# EasyEDA_sensor_project.net
KiCad netlist of a schematic drawn in EasyEDA Pro
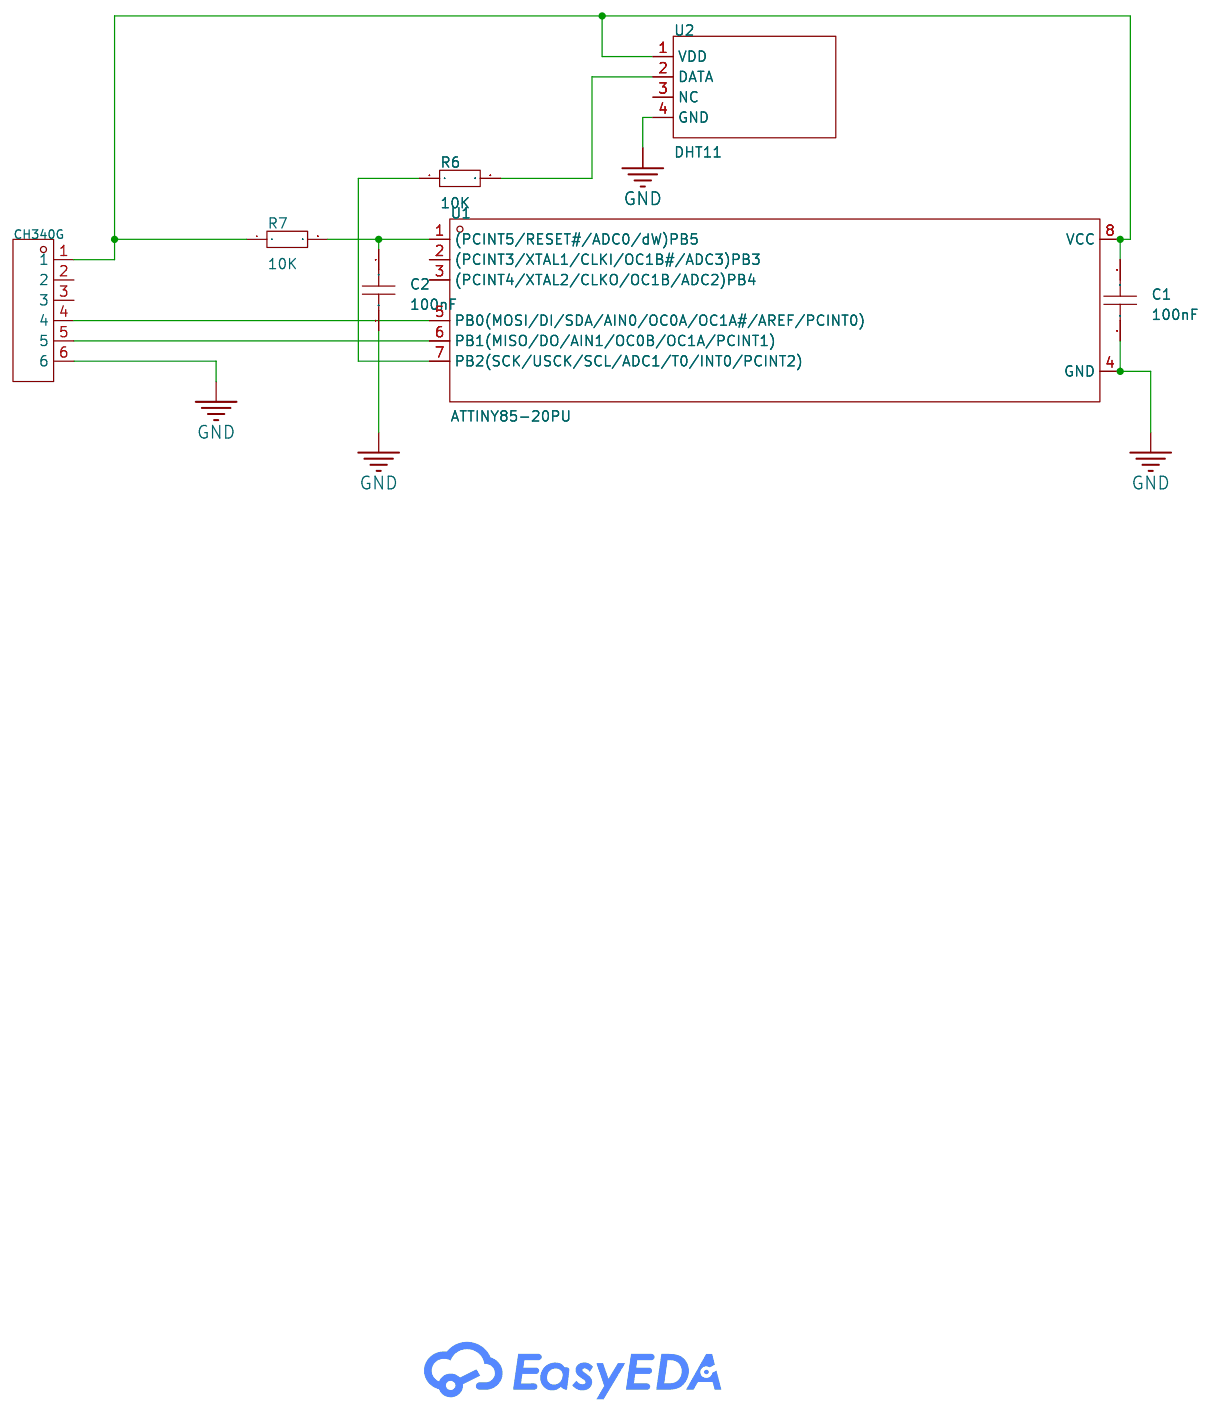
[diagram p0: schematic sheet]

(export (version "E")
  (design (tool "Eeschema 10.0.6"))
  (components
    (comp (ref "C1")
      (value "100nF")
      (footprint "easyedapro:C0201")
      (libsource (lib "easyedapro") (part "CAP"))
    )
    (comp (ref "C2")
      (value "100nF")
      (footprint "easyedapro:C0201")
      (libsource (lib "easyedapro") (part "CAP"))
    )
    (comp (ref "CH340G")
      (value "~")
      (footprint "easyedapro:HDR-TH_6P-P2.54-V-F")
      (libsource (lib "easyedapro") (part "Header-Female-2.54_1x6"))
    )
    (comp (ref "R6") (value "10K") (footprint "easyedapro:R0603") (libsource (lib "easyedapro") (part "Res")))
    (comp (ref "R7") (value "10K") (footprint "easyedapro:R0603") (libsource (lib "easyedapro") (part "Res")))
    (comp (ref "U1")
      (value "ATTINY85-20PU")
      (footprint "easyedapro:PDIP-8_L9.3-W6.4-P2.54-LS7.9-BL-1")
      (fields (field (name "Manufacturer") "MICROCHIP(美国微芯)"))
      (libsource (lib "easyedapro") (part "ATTINY85-20PU"))
    )
    (comp (ref "U2")
      (value "DHT11")
      (footprint "easyedapro:SENSOR-TH_DHT11")
      (fields (field (name "Manufacturer") "广州奥松"))
      (libsource (lib "easyedapro") (part "DHT11"))
    )
  )
  (nets
    (net (code "1") (name "GND") (class "Default")
      (node (ref "C1") (pin "2") (pinfunction "2_2") (pintype "input"))
      (node (ref "C2") (pin "2") (pinfunction "2_2") (pintype "input"))
      (node (ref "CH340G") (pin "6") (pinfunction "6_6") (pintype "input"))
      (node (ref "U1") (pin "4") (pinfunction "GND_4") (pintype "unspecified"))
      (node (ref "U2") (pin "4") (pinfunction "GND_4") (pintype "unspecified"))
    )
    (net (code "2") (name "Net-(U1-(PCINT5{slash}RESET#{slash}ADC0{slash}dW)PB5)") (class "Default")
      (node (ref "C2") (pin "1") (pinfunction "1_1") (pintype "input"))
      (node (ref "R7") (pin "2") (pinfunction "2_2") (pintype "input"))
      (node (ref "U1") (pin "1") (pinfunction "(PCINT5/RESET#/ADC0/dW)PB5_1") (pintype "unspecified"))
    )
    (net (code "3") (name "Net-(U1-PB0(MOSI{slash}DI{slash}SDA{slash}AIN0{slash}OC0A{slash}OC1A#{slash}AREF{slash}PCINT0))") (class "Default")
      (node (ref "CH340G") (pin "4") (pinfunction "4_4") (pintype "input"))
      (node (ref "U1") (pin "5") (pinfunction "PB0(MOSI/DI/SDA/AIN0/OC0A/OC1A#/AREF/PCINT0)_5") (pintype "unspecified"))
    )
    (net (code "4") (name "Net-(U1-PB1(MISO{slash}DO{slash}AIN1{slash}OC0B{slash}OC1A{slash}PCINT1))") (class "Default")
      (node (ref "CH340G") (pin "5") (pinfunction "5_5") (pintype "input"))
      (node (ref "U1") (pin "6") (pinfunction "PB1(MISO/DO/AIN1/OC0B/OC1A/PCINT1)_6") (pintype "unspecified"))
    )
    (net (code "5") (name "Net-(U1-PB2(SCK{slash}USCK{slash}SCL{slash}ADC1{slash}T0{slash}INT0{slash}PCINT2))") (class "Default")
      (node (ref "R6") (pin "1") (pinfunction "1_1") (pintype "input"))
      (node (ref "U1") (pin "7") (pinfunction "PB2(SCK/USCK/SCL/ADC1/T0/INT0/PCINT2)_7") (pintype "unspecified"))
    )
    (net (code "6") (name "Net-(U1-VCC)") (class "Default")
      (node (ref "C1") (pin "1") (pinfunction "1_1") (pintype "input"))
      (node (ref "CH340G") (pin "1") (pinfunction "1_1") (pintype "input"))
      (node (ref "R7") (pin "1") (pinfunction "1_1") (pintype "input"))
      (node (ref "U1") (pin "8") (pinfunction "VCC_8") (pintype "unspecified"))
      (node (ref "U2") (pin "1") (pinfunction "VDD_1") (pintype "unspecified"))
    )
    (net (code "7") (name "Net-(U2-DATA)") (class "Default")
      (node (ref "R6") (pin "2") (pinfunction "2_2") (pintype "input"))
      (node (ref "U2") (pin "2") (pinfunction "DATA_2") (pintype "unspecified"))
    )
    (net (code "8") (name "unconnected-(CH340G-Pad2)") (class "Default")
      (node (ref "CH340G") (pin "2") (pinfunction "2_2") (pintype "input"))
    )
    (net (code "9") (name "unconnected-(CH340G-Pad3)") (class "Default")
      (node (ref "CH340G") (pin "3") (pinfunction "3_3") (pintype "input"))
    )
    (net (code "10") (name "unconnected-(U1-(PCINT3{slash}XTAL1{slash}CLKI{slash}OC1B#{slash}ADC3)PB3-Pad2)") (class "Default")
      (node (ref "U1") (pin "2") (pinfunction "(PCINT3/XTAL1/CLKI/OC1B#/ADC3)PB3_2") (pintype "unspecified"))
    )
    (net (code "11") (name "unconnected-(U1-(PCINT4{slash}XTAL2{slash}CLKO{slash}OC1B{slash}ADC2)PB4-Pad3)") (class "Default")
      (node (ref "U1") (pin "3") (pinfunction "(PCINT4/XTAL2/CLKO/OC1B/ADC2)PB4_3") (pintype "unspecified"))
    )
    (net (code "12") (name "unconnected-(U2-NC-Pad3)") (class "Default")
      (node (ref "U2") (pin "3") (pinfunction "NC_3") (pintype "unspecified"))
    )
  )
)
